# base-board_2.net
KiCad netlist of a schematic drawn in Altium Designer
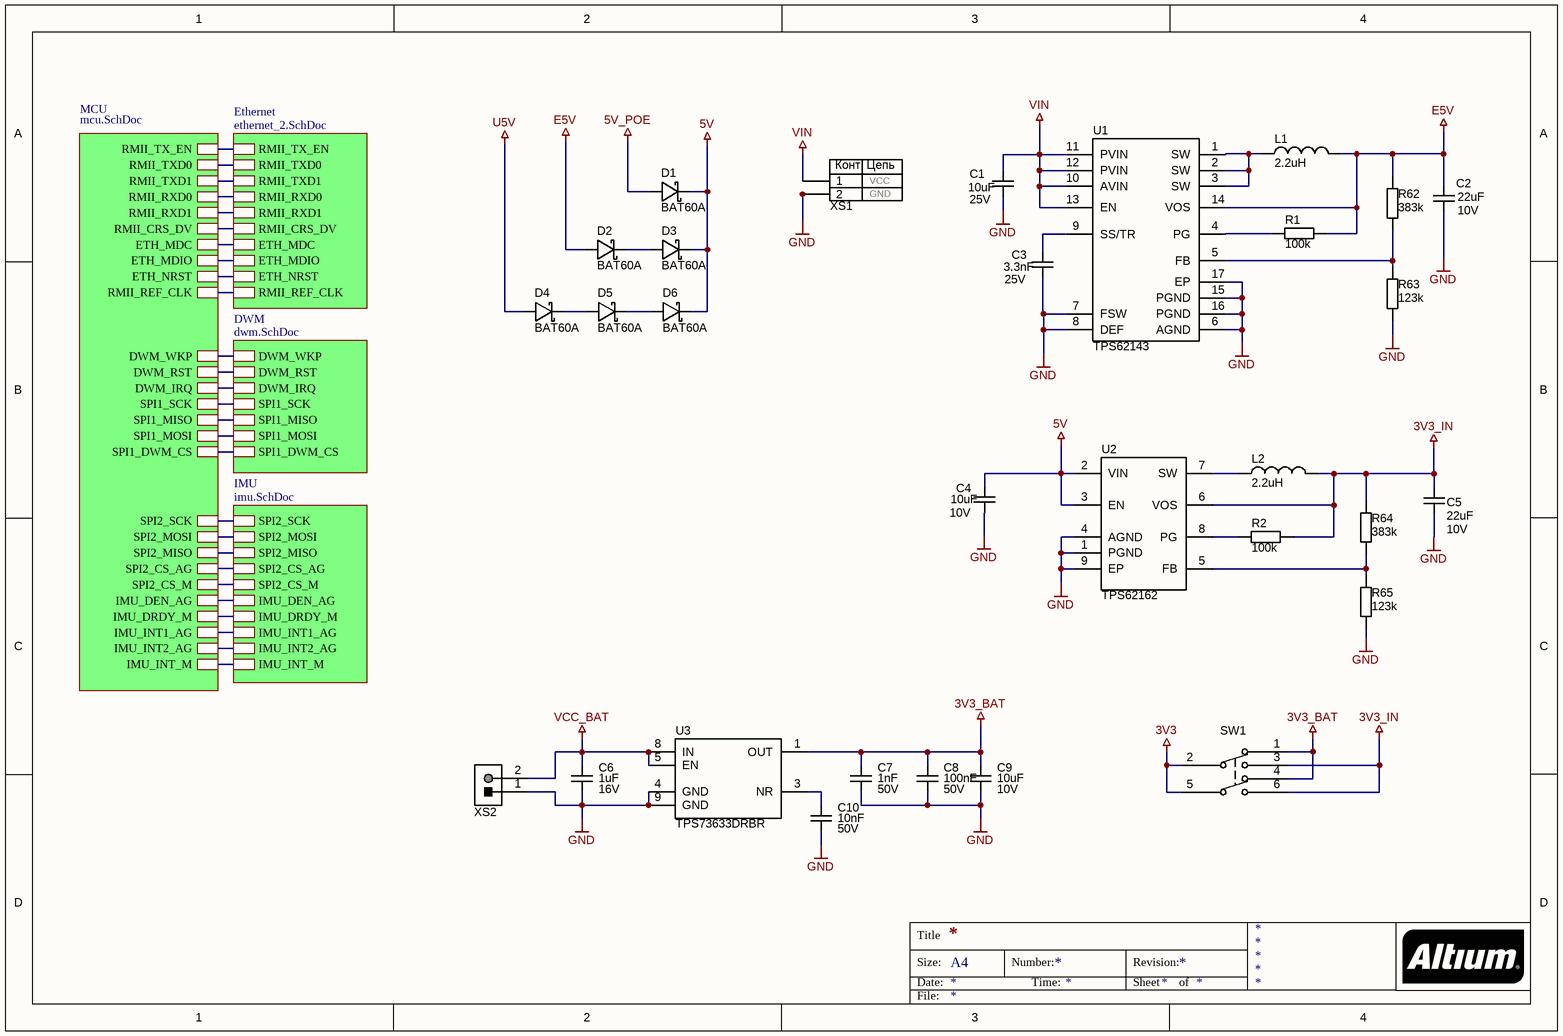
[diagram p0: base-board_2.SchDoc]

(export (version "E")
  (design (tool "Eeschema 10.0.6"))
  (components
    (comp (ref "C1")
      (value "10uF")
      (footprint "C1210")
      (fields (field (name "VOLTAGE") "25V") (field (name "Comment") "C1210"))
      (libsource (lib "DZ_LIB") (part "C1210"))
    )
    (comp (ref "C2")
      (value "22uF")
      (footprint "C1210")
      (fields (field (name "VOLTAGE") "10V") (field (name "Comment") "C1210"))
      (libsource (lib "DZ_LIB") (part "C1210"))
    )
    (comp (ref "C3")
      (value "3.3nF")
      (footprint "C0603")
      (fields (field (name "VOLTAGE") "25V") (field (name "Comment") "C0603"))
      (libsource (lib "DZ_LIB") (part "C0603"))
    )
    (comp (ref "C4")
      (value "10uF")
      (footprint "C0805")
      (fields (field (name "VOLTAGE") "10V") (field (name "Comment") "C0805"))
      (libsource (lib "DZ_LIB") (part "C0805"))
    )
    (comp (ref "C5")
      (value "22uF")
      (footprint "C0805")
      (fields (field (name "VOLTAGE") "10V") (field (name "Comment") "C0805"))
      (libsource (lib "DZ_LIB") (part "C0805"))
    )
    (comp (ref "C6")
      (value "1uF")
      (footprint "C0805")
      (fields (field (name "VOLTAGE") "16V") (field (name "Comment") "C0805"))
      (libsource (lib "DZ_LIB") (part "C0805"))
    )
    (comp (ref "C7")
      (value "1nF")
      (footprint "C0805")
      (fields (field (name "VOLTAGE") "50V") (field (name "Comment") "C0805"))
      (libsource (lib "DZ_LIB") (part "C0805"))
    )
    (comp (ref "C8")
      (value "100nF")
      (footprint "C0603")
      (fields (field (name "VOLTAGE") "50V") (field (name "Comment") "C0603"))
      (libsource (lib "DZ_LIB") (part "C0603"))
    )
    (comp (ref "C9")
      (value "10uF")
      (footprint "C0603")
      (fields (field (name "VOLTAGE") "10V") (field (name "Comment") "C0603"))
      (libsource (lib "DZ_LIB") (part "C0603"))
    )
    (comp (ref "C10")
      (value "10nF")
      (footprint "C0603")
      (fields (field (name "VOLTAGE") "50V") (field (name "Comment") "C0603"))
      (libsource (lib "DZ_LIB") (part "C0603"))
    )
    (comp (ref "D1")
      (value "BAT60A")
      (footprint "SOD-323-2")
      (description "Shottky Diode 10V 3A")
      (libsource (lib "DZ_LIB") (part "BAT60J"))
    )
    (comp (ref "D2")
      (value "BAT60A")
      (footprint "SOD-323-2")
      (description "Shottky Diode 10V 3A")
      (libsource (lib "DZ_LIB") (part "BAT60J"))
    )
    (comp (ref "D3")
      (value "BAT60A")
      (footprint "SOD-323-2")
      (description "Shottky Diode 10V 3A")
      (libsource (lib "DZ_LIB") (part "BAT60J"))
    )
    (comp (ref "D4")
      (value "BAT60A")
      (footprint "SOD-323-2")
      (description "Shottky Diode 10V 3A")
      (libsource (lib "DZ_LIB") (part "BAT60J"))
    )
    (comp (ref "D5")
      (value "BAT60A")
      (footprint "SOD-323-2")
      (description "Shottky Diode 10V 3A")
      (libsource (lib "DZ_LIB") (part "BAT60J"))
    )
    (comp (ref "D6")
      (value "BAT60A")
      (footprint "SOD-323-2")
      (description "Shottky Diode 10V 3A")
      (libsource (lib "DZ_LIB") (part "BAT60J"))
    )
    (comp (ref "L1")
      (value "2.2uH")
      (footprint "IND2220")
      (description "FIXED IND 2.2UH 2.5A 31 MOHM SMD")
      (fields (field (name "Comment") "LQH55PN2R2NR0"))
      (libsource (lib "DZ_LIB") (part "LQH55PN2R2NR0"))
    )
    (comp (ref "L2")
      (value "2.2uH")
      (footprint "IND2220")
      (description "FIXED IND 2.2UH 2.5A 31 MOHM SMD")
      (fields (field (name "Comment") "LQH55PN2R2NR0"))
      (libsource (lib "DZ_LIB") (part "LQH55PN2R2NR0"))
    )
    (comp (ref "R1")
      (value "100k")
      (footprint "SMD0603")
      (fields (field (name "Comment") "R0603"))
      (libsource (lib "DZ_LIB") (part "R0603"))
    )
    (comp (ref "R2")
      (value "100k")
      (footprint "SMD0603")
      (fields (field (name "Comment") "R0603"))
      (libsource (lib "DZ_LIB") (part "R0603"))
    )
    (comp (ref "R62")
      (value "383k")
      (footprint "SMD0603")
      (fields (field (name "Comment") "R0603"))
      (libsource (lib "") (part "R0603_1"))
    )
    (comp (ref "R63")
      (value "123k")
      (footprint "SMD0603")
      (fields (field (name "Comment") "R0603"))
      (libsource (lib "") (part "R0603_1"))
    )
    (comp (ref "R64")
      (value "383k")
      (footprint "SMD0603")
      (fields (field (name "Comment") "R0603"))
      (libsource (lib "") (part "R0603_1"))
    )
    (comp (ref "R65")
      (value "123k")
      (footprint "SMD0603")
      (fields (field (name "Comment") "R0603"))
      (libsource (lib "") (part "R0603_1"))
    )
    (comp (ref "SW1")
      (value "JS202011SCQN")
      (footprint "JS202011SCQN")
      (description "Switch Slide DPDT, 0.3 A, 6 V, -40 to 85 degC, 6-Pin SMD, RoHS, Tape and Reel")
      (fields (field (name "MANUFACTURER") "C&K Components"))
      (libsource (lib "DZ_LIB") (part "JS202011SCQN"))
    )
    (comp (ref "U1")
      (value "TPS62143")
      (footprint "QFN-16")
      (description "Buck 2A TI Fix 5V")
      (libsource (lib "DZ_LIB") (part "TPS62143RGT16"))
    )
    (comp (ref "U2")
      (value "TPS62162")
      (footprint "SON-8")
      (description "Buck 1A TI Fix 3.3V")
      (libsource (lib "DZ_LIB") (part "TPS62162DSG8"))
    )
    (comp (ref "U3")
      (value "TPS73633DRBR")
      (footprint "VSON-8")
      (description "IC REG LINEAR 3.3V 400MA 8SON")
      (libsource (lib "DZ_LIB") (part "TPS73633DRBR"))
    )
    (comp (ref "XS1")
      (value "PowerJack")
      (footprint "PowerJack")
      (libsource (lib "DZ_LIB") (part "PowerJack"))
    )
    (comp (ref "XS2")
      (value "S2B-PH-K-S")
      (footprint "S2B-PH-K-S")
      (fields (field (name "TOLERANCE") "20%"))
      (libsource (lib "DZ_LIB") (part "S2B-PH-K-S"))
    )
  )
  (nets
    (net (code "28") (name "3V3") (class "Default")
      (node (ref "SW1") (pin "2") (pinfunction "COM_2") (pintype "passive"))
      (node (ref "SW1") (pin "5") (pinfunction "COM_5") (pintype "passive"))
    )
    (net (code "29") (name "3V3_BAT") (class "Default")
      (node (ref "C7") (pin "2") (pinfunction "2_2") (pintype "passive"))
      (node (ref "C8") (pin "2") (pinfunction "2_2") (pintype "passive"))
      (node (ref "C9") (pin "2") (pinfunction "2_2") (pintype "passive"))
      (node (ref "SW1") (pin "1") (pinfunction "1_1") (pintype "passive"))
      (node (ref "SW1") (pin "4") (pinfunction "4_4") (pintype "passive"))
      (node (ref "U3") (pin "1") (pinfunction "OUT_1") (pintype "passive"))
    )
    (net (code "30") (name "3V3_IN") (class "Default")
      (node (ref "C5") (pin "2") (pinfunction "2_2") (pintype "passive"))
      (node (ref "L2") (pin "2") (pinfunction "2_2") (pintype "passive"))
      (node (ref "R2") (pin "2") (pinfunction "2_2") (pintype "passive"))
      (node (ref "R64") (pin "2") (pinfunction "2_2") (pintype "passive"))
      (node (ref "SW1") (pin "3") (pinfunction "3_3") (pintype "passive"))
      (node (ref "SW1") (pin "6") (pinfunction "6_6") (pintype "passive"))
      (node (ref "U2") (pin "6") (pinfunction "VOS_6") (pintype "passive"))
    )
    (net (code "31") (name "5V") (class "Default")
      (node (ref "C4") (pin "2") (pinfunction "2_2") (pintype "passive"))
      (node (ref "D1") (pin "2") (pinfunction "K_2") (pintype "passive"))
      (node (ref "D3") (pin "2") (pinfunction "K_2") (pintype "passive"))
      (node (ref "D6") (pin "2") (pinfunction "K_2") (pintype "passive"))
      (node (ref "U2") (pin "2") (pinfunction "VIN_2") (pintype "power_in"))
      (node (ref "U2") (pin "3") (pinfunction "EN_3") (pintype "passive"))
    )
    (net (code "32") (name "5V_POE") (class "Default")
      (node (ref "D1") (pin "1") (pinfunction "A_1") (pintype "passive"))
    )
    (net (code "33") (name "E5V") (class "Default")
      (node (ref "C2") (pin "2") (pinfunction "2_2") (pintype "passive"))
      (node (ref "D2") (pin "1") (pinfunction "A_1") (pintype "passive"))
      (node (ref "L1") (pin "2") (pinfunction "2_2") (pintype "passive"))
      (node (ref "R1") (pin "2") (pinfunction "2_2") (pintype "passive"))
      (node (ref "R62") (pin "2") (pinfunction "2_2") (pintype "passive"))
      (node (ref "U1") (pin "14") (pinfunction "VOS_14") (pintype "passive"))
    )
    (net (code "34") (name "GND") (class "Default")
      (node (ref "C1") (pin "1") (pinfunction "1_1") (pintype "passive"))
      (node (ref "C10") (pin "1") (pinfunction "1_1") (pintype "passive"))
      (node (ref "C2") (pin "1") (pinfunction "1_1") (pintype "passive"))
      (node (ref "C3") (pin "1") (pinfunction "1_1") (pintype "passive"))
      (node (ref "C4") (pin "1") (pinfunction "1_1") (pintype "passive"))
      (node (ref "C5") (pin "1") (pinfunction "1_1") (pintype "passive"))
      (node (ref "C6") (pin "1") (pinfunction "1_1") (pintype "passive"))
      (node (ref "C7") (pin "1") (pinfunction "1_1") (pintype "passive"))
      (node (ref "C8") (pin "1") (pinfunction "1_1") (pintype "passive"))
      (node (ref "C9") (pin "1") (pinfunction "1_1") (pintype "passive"))
      (node (ref "R63") (pin "1") (pinfunction "1_1") (pintype "passive"))
      (node (ref "R65") (pin "1") (pinfunction "1_1") (pintype "passive"))
      (node (ref "U1") (pin "15") (pinfunction "PGND_15") (pintype "passive"))
      (node (ref "U1") (pin "16") (pinfunction "PGND_16") (pintype "passive"))
      (node (ref "U1") (pin "17") (pinfunction "EP_17") (pintype "passive"))
      (node (ref "U1") (pin "6") (pinfunction "AGND_6") (pintype "passive"))
      (node (ref "U1") (pin "7") (pinfunction "FSW_7") (pintype "passive"))
      (node (ref "U1") (pin "8") (pinfunction "DEF_8") (pintype "passive"))
      (node (ref "U2") (pin "1") (pinfunction "PGND_1") (pintype "power_in"))
      (node (ref "U2") (pin "4") (pinfunction "AGND_4") (pintype "power_in"))
      (node (ref "U2") (pin "9") (pinfunction "EP_9") (pintype "power_in"))
      (node (ref "U3") (pin "4") (pinfunction "GND_4") (pintype "passive"))
      (node (ref "U3") (pin "9") (pinfunction "GND_9") (pintype "passive"))
      (node (ref "XS1") (pin "2") (pinfunction "2_2") (pintype "passive"))
      (node (ref "XS1") (pin "3") (pinfunction "3_3") (pintype "passive"))
      (node (ref "XS2") (pin "1") (pinfunction "1_1") (pintype "passive"))
    )
    (net (code "35") (name "Net-(D2-K)") (class "Default")
      (node (ref "D2") (pin "2") (pinfunction "K_2") (pintype "passive"))
      (node (ref "D3") (pin "1") (pinfunction "A_1") (pintype "passive"))
    )
    (net (code "36") (name "Net-(D4-K)") (class "Default")
      (node (ref "D4") (pin "2") (pinfunction "K_2") (pintype "passive"))
      (node (ref "D5") (pin "1") (pinfunction "A_1") (pintype "passive"))
    )
    (net (code "37") (name "Net-(D5-K)") (class "Default")
      (node (ref "D5") (pin "2") (pinfunction "K_2") (pintype "passive"))
      (node (ref "D6") (pin "1") (pinfunction "A_1") (pintype "passive"))
    )
    (net (code "38") (name "Net-(L1-Pad1)") (class "Default")
      (node (ref "L1") (pin "1") (pinfunction "1_1") (pintype "passive"))
      (node (ref "U1") (pin "1") (pinfunction "SW_1") (pintype "passive"))
      (node (ref "U1") (pin "2") (pinfunction "SW_2") (pintype "passive"))
      (node (ref "U1") (pin "3") (pinfunction "SW_3") (pintype "passive"))
    )
    (net (code "39") (name "Net-(U1-FB)") (class "Default")
      (node (ref "R62") (pin "1") (pinfunction "1_1") (pintype "passive"))
      (node (ref "R63") (pin "2") (pinfunction "2_2") (pintype "passive"))
      (node (ref "U1") (pin "5") (pinfunction "FB_5") (pintype "passive"))
    )
    (net (code "40") (name "Net-(U1-PG)") (class "Default")
      (node (ref "R1") (pin "1") (pinfunction "1_1") (pintype "passive"))
      (node (ref "U1") (pin "4") (pinfunction "PG_4") (pintype "passive"))
    )
    (net (code "41") (name "Net-(U1-SS{slash}TR)") (class "Default")
      (node (ref "C3") (pin "2") (pinfunction "2_2") (pintype "passive"))
      (node (ref "U1") (pin "9") (pinfunction "SS/TR_9") (pintype "passive"))
    )
    (net (code "42") (name "Net-(U2-FB)") (class "Default")
      (node (ref "R64") (pin "1") (pinfunction "1_1") (pintype "passive"))
      (node (ref "R65") (pin "2") (pinfunction "2_2") (pintype "passive"))
      (node (ref "U2") (pin "5") (pinfunction "FB_5") (pintype "passive"))
    )
    (net (code "43") (name "Net-(U2-PG)") (class "Default")
      (node (ref "R2") (pin "1") (pinfunction "1_1") (pintype "passive"))
      (node (ref "U2") (pin "8") (pinfunction "PG_8") (pintype "tri_state"))
    )
    (net (code "44") (name "Net-(U2-SW)") (class "Default")
      (node (ref "L2") (pin "1") (pinfunction "1_1") (pintype "passive"))
      (node (ref "U2") (pin "7") (pinfunction "SW_7") (pintype "power_in"))
    )
    (net (code "45") (name "Net-(U3-NR)") (class "Default")
      (node (ref "C10") (pin "2") (pinfunction "2_2") (pintype "passive"))
      (node (ref "U3") (pin "3") (pinfunction "NR_3") (pintype "passive"))
    )
    (net (code "46") (name "U5V") (class "Default")
      (node (ref "D4") (pin "1") (pinfunction "A_1") (pintype "passive"))
    )
    (net (code "47") (name "VCC_BAT") (class "Default")
      (node (ref "C6") (pin "2") (pinfunction "2_2") (pintype "passive"))
      (node (ref "U3") (pin "5") (pinfunction "EN_5") (pintype "passive"))
      (node (ref "U3") (pin "8") (pinfunction "IN_8") (pintype "passive"))
      (node (ref "XS2") (pin "2") (pinfunction "2_2") (pintype "passive"))
    )
    (net (code "48") (name "VIN") (class "Default")
      (node (ref "C1") (pin "2") (pinfunction "2_2") (pintype "passive"))
      (node (ref "U1") (pin "10") (pinfunction "AVIN_10") (pintype "passive"))
      (node (ref "U1") (pin "11") (pinfunction "PVIN_11") (pintype "passive"))
      (node (ref "U1") (pin "12") (pinfunction "PVIN_12") (pintype "passive"))
      (node (ref "U1") (pin "13") (pinfunction "EN_13") (pintype "passive"))
      (node (ref "XS1") (pin "1") (pinfunction "1_1") (pintype "passive"))
    )
  )
)
